# LPDDR4_SDRAM_2.net
KiCad netlist of a schematic drawn in Altium Designer
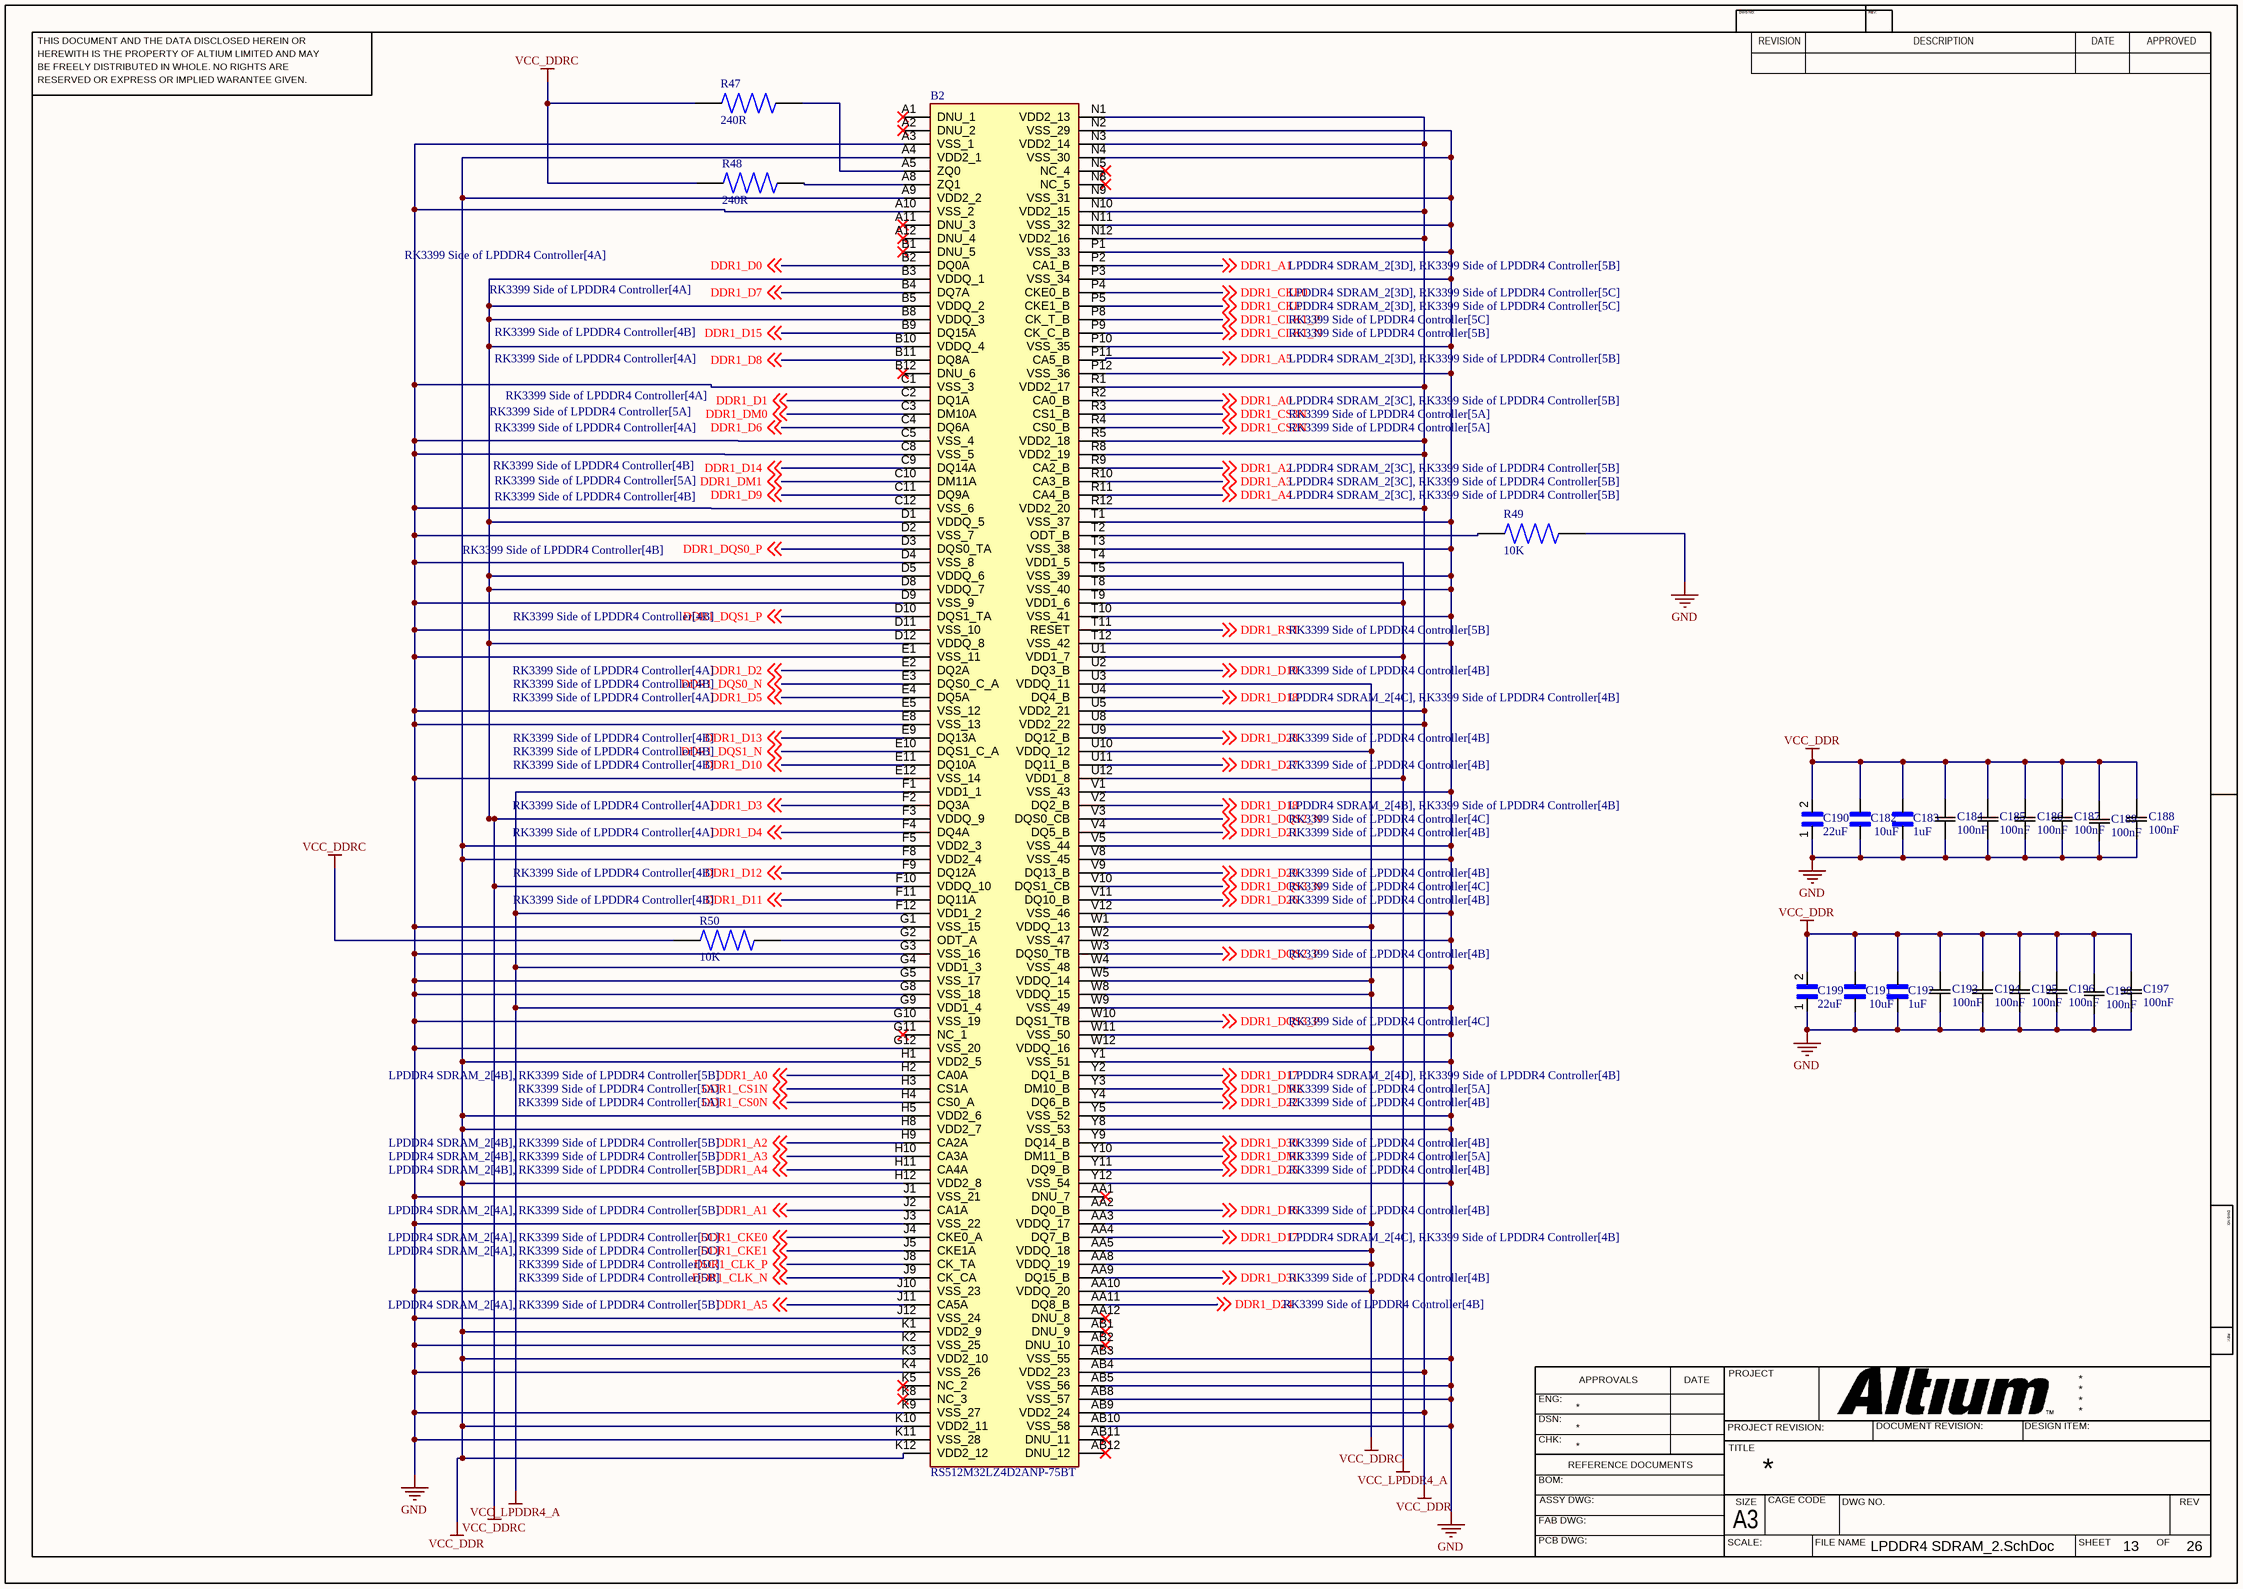
[diagram p0: LPDDR4 SDRAM_2.SchDoc]

(export (version "E")
  (design (tool "Eeschema 10.0.6"))
  (components
    (comp (ref "B2")
      (value "RS512M32LZ4D2ANP-75BT")
      (footprint "BGA200C65P12X22_1000X1500X100")
      (description "BGA-200 New Arrivals ROHS")
      (libsource (lib "RS512M32LZ4D2ANP-75BT") (part "RS512M32LZ4D2ANP-75BT"))
    )
    (comp (ref "C182")
      (value "10uF")
      (footprint "CAPC1005X70N")
      (description "10 ÂµF Â±20% 6.3V Ceramic Capacitor X5R 0402 (1005 Metric)")
      (fields (field (name "MF") "Samsung") (field (name "MP") "CL05A106MQ5NUNC"))
      (libsource (lib "CL05A106MQ5NUNC") (part "CL05A106MQ5NUNC"))
    )
    (comp (ref "C183")
      (value "1uF")
      (footprint "CAPC1005X56N")
      (description "1 ÂµF Â±10% 10V Ceramic Capacitor X5R 0402 (1005 Metric)")
      (fields (field (name "MF") "AVX") (field (name "MP") "0402ZD105KAT4A"))
      (libsource (lib "0402ZD105KAT4A") (part "0402ZD105KAT4A"))
    )
    (comp (ref "C184")
      (value "100nF")
      (footprint "CAP_1005_TDK")
      (description "Description")
      (fields
        (field (name "MANUFACTURER_PART_NUMBER") "C1005X7R1H104M050BB")
        (field (name "COPYRIGHT") "Copyright (C) 2025 Ultra Librarian. All rights reserved.")
      )
      (libsource (lib "C1005X7R1H104M050BB") (part "C1005X7R1H104M050BB"))
    )
    (comp (ref "C185")
      (value "100nF")
      (footprint "CAP_1005_TDK")
      (description "Description")
      (fields
        (field (name "MANUFACTURER_PART_NUMBER") "C1005X7R1H104M050BB")
        (field (name "COPYRIGHT") "Copyright (C) 2025 Ultra Librarian. All rights reserved.")
      )
      (libsource (lib "C1005X7R1H104M050BB") (part "C1005X7R1H104M050BB"))
    )
    (comp (ref "C186")
      (value "100nF")
      (footprint "CAP_1005_TDK")
      (description "Description")
      (fields
        (field (name "MANUFACTURER_PART_NUMBER") "C1005X7R1H104M050BB")
        (field (name "COPYRIGHT") "Copyright (C) 2025 Ultra Librarian. All rights reserved.")
      )
      (libsource (lib "C1005X7R1H104M050BB") (part "C1005X7R1H104M050BB"))
    )
    (comp (ref "C187")
      (value "100nF")
      (footprint "CAP_1005_TDK")
      (description "Description")
      (fields
        (field (name "MANUFACTURER_PART_NUMBER") "C1005X7R1H104M050BB")
        (field (name "COPYRIGHT") "Copyright (C) 2025 Ultra Librarian. All rights reserved.")
      )
      (libsource (lib "C1005X7R1H104M050BB") (part "C1005X7R1H104M050BB"))
    )
    (comp (ref "C188")
      (value "100nF")
      (footprint "CAP_1005_TDK")
      (description "Description")
      (fields
        (field (name "MANUFACTURER_PART_NUMBER") "C1005X7R1H104M050BB")
        (field (name "COPYRIGHT") "Copyright (C) 2025 Ultra Librarian. All rights reserved.")
      )
      (libsource (lib "C1005X7R1H104M050BB") (part "C1005X7R1H104M050BB"))
    )
    (comp (ref "C189")
      (value "100nF")
      (footprint "CAP_1005_TDK")
      (description "Description")
      (fields
        (field (name "MANUFACTURER_PART_NUMBER") "C1005X7R1H104M050BB")
        (field (name "COPYRIGHT") "Copyright (C) 2025 Ultra Librarian. All rights reserved.")
      )
      (libsource (lib "C1005X7R1H104M050BB") (part "C1005X7R1H104M050BB"))
    )
    (comp (ref "C190")
      (value "22uF")
      (footprint "CAPC6050X550N")
      (description "22ÂµF Â±20% 50V Ceramic Capacitor X7S Stacked SMD, 2 J-Lead")
      (fields (field (name "MP") "CKG57NX7S1H226M500JJ"))
      (libsource (lib "CKG57NX7S1H226M500JJ") (part "CKG57NX7S1H226M500JJ"))
    )
    (comp (ref "C191")
      (value "10uF")
      (footprint "CAPC1005X70N")
      (description "10 ÂµF Â±20% 6.3V Ceramic Capacitor X5R 0402 (1005 Metric)")
      (fields (field (name "MF") "Samsung") (field (name "MP") "CL05A106MQ5NUNC"))
      (libsource (lib "CL05A106MQ5NUNC") (part "CL05A106MQ5NUNC"))
    )
    (comp (ref "C192")
      (value "1uF")
      (footprint "CAPC1005X56N")
      (description "1 ÂµF Â±10% 10V Ceramic Capacitor X5R 0402 (1005 Metric)")
      (fields (field (name "MF") "AVX") (field (name "MP") "0402ZD105KAT4A"))
      (libsource (lib "0402ZD105KAT4A") (part "0402ZD105KAT4A"))
    )
    (comp (ref "C193")
      (value "100nF")
      (footprint "CAP_1005_TDK")
      (description "Description")
      (fields
        (field (name "MANUFACTURER_PART_NUMBER") "C1005X7R1H104M050BB")
        (field (name "COPYRIGHT") "Copyright (C) 2025 Ultra Librarian. All rights reserved.")
      )
      (libsource (lib "C1005X7R1H104M050BB") (part "C1005X7R1H104M050BB"))
    )
    (comp (ref "C194")
      (value "100nF")
      (footprint "CAP_1005_TDK")
      (description "Description")
      (fields
        (field (name "MANUFACTURER_PART_NUMBER") "C1005X7R1H104M050BB")
        (field (name "COPYRIGHT") "Copyright (C) 2025 Ultra Librarian. All rights reserved.")
      )
      (libsource (lib "C1005X7R1H104M050BB") (part "C1005X7R1H104M050BB"))
    )
    (comp (ref "C195")
      (value "100nF")
      (footprint "CAP_1005_TDK")
      (description "Description")
      (fields
        (field (name "MANUFACTURER_PART_NUMBER") "C1005X7R1H104M050BB")
        (field (name "COPYRIGHT") "Copyright (C) 2025 Ultra Librarian. All rights reserved.")
      )
      (libsource (lib "C1005X7R1H104M050BB") (part "C1005X7R1H104M050BB"))
    )
    (comp (ref "C196")
      (value "100nF")
      (footprint "CAP_1005_TDK")
      (description "Description")
      (fields
        (field (name "MANUFACTURER_PART_NUMBER") "C1005X7R1H104M050BB")
        (field (name "COPYRIGHT") "Copyright (C) 2025 Ultra Librarian. All rights reserved.")
      )
      (libsource (lib "C1005X7R1H104M050BB") (part "C1005X7R1H104M050BB"))
    )
    (comp (ref "C197")
      (value "100nF")
      (footprint "CAP_1005_TDK")
      (description "Description")
      (fields
        (field (name "MANUFACTURER_PART_NUMBER") "C1005X7R1H104M050BB")
        (field (name "COPYRIGHT") "Copyright (C) 2025 Ultra Librarian. All rights reserved.")
      )
      (libsource (lib "C1005X7R1H104M050BB") (part "C1005X7R1H104M050BB"))
    )
    (comp (ref "C198")
      (value "100nF")
      (footprint "CAP_1005_TDK")
      (description "Description")
      (fields
        (field (name "MANUFACTURER_PART_NUMBER") "C1005X7R1H104M050BB")
        (field (name "COPYRIGHT") "Copyright (C) 2025 Ultra Librarian. All rights reserved.")
      )
      (libsource (lib "C1005X7R1H104M050BB") (part "C1005X7R1H104M050BB"))
    )
    (comp (ref "C199")
      (value "22uF")
      (footprint "CAPC6050X550N")
      (description "22ÂµF Â±20% 50V Ceramic Capacitor X7S Stacked SMD, 2 J-Lead")
      (fields (field (name "MP") "CKG57NX7S1H226M500JJ"))
      (libsource (lib "CKG57NX7S1H226M500JJ") (part "CKG57NX7S1H226M500JJ"))
    )
    (comp (ref "R47")
      (value "240R")
      (footprint "RESC1608X50N")
      (fields (field (name "MP") "ERA6AED241V"))
      (libsource (lib "ERA6AED241V") (part "ERA6AED241V"))
    )
    (comp (ref "R48")
      (value "240R")
      (footprint "RESC1608X50N")
      (fields (field (name "MP") "ERA6AED241V"))
      (libsource (lib "ERA6AED241V") (part "ERA6AED241V"))
    )
    (comp (ref "R49")
      (value "10K")
      (footprint "RESC1608X55N")
      (description "1 kOhms Â±1% 0.1W, 1/10W Chip Resistor 0603 (1608 Metric) - Thick Film")
      (fields (field (name "MF") "Vishay") (field (name "MP") "CRCW06031K00FKECC"))
      (libsource (lib "CRCW06031K00FKECC") (part "CRCW06031K00FKECC"))
    )
    (comp (ref "R50")
      (value "10K")
      (footprint "RESC1608X55N")
      (description "1 kOhms Â±1% 0.1W, 1/10W Chip Resistor 0603 (1608 Metric) - Thick Film")
      (fields (field (name "MF") "Vishay") (field (name "MP") "CRCW06031K00FKECC"))
      (libsource (lib "CRCW06031K00FKECC") (part "CRCW06031K00FKECC"))
    )
  )
  (nets
    (net (code "1") (name "DDR1_A0") (class "Default")
      (node (ref "B2") (pin "H2") (pinfunction "CA0A_H2") (pintype "passive"))
      (node (ref "B2") (pin "R2") (pinfunction "CA0_B_R2") (pintype "passive"))
    )
    (net (code "2") (name "DDR1_A1") (class "Default")
      (node (ref "B2") (pin "J2") (pinfunction "CA1A_J2") (pintype "passive"))
      (node (ref "B2") (pin "P2") (pinfunction "CA1_B_P2") (pintype "passive"))
    )
    (net (code "3") (name "DDR1_A2") (class "Default")
      (node (ref "B2") (pin "H9") (pinfunction "CA2A_H9") (pintype "passive"))
      (node (ref "B2") (pin "R9") (pinfunction "CA2_B_R9") (pintype "passive"))
    )
    (net (code "4") (name "DDR1_A3") (class "Default")
      (node (ref "B2") (pin "H10") (pinfunction "CA3A_H10") (pintype "passive"))
      (node (ref "B2") (pin "R10") (pinfunction "CA3_B_R10") (pintype "passive"))
    )
    (net (code "5") (name "DDR1_A4") (class "Default")
      (node (ref "B2") (pin "H11") (pinfunction "CA4A_H11") (pintype "passive"))
      (node (ref "B2") (pin "R11") (pinfunction "CA4_B_R11") (pintype "passive"))
    )
    (net (code "6") (name "DDR1_A5") (class "Default")
      (node (ref "B2") (pin "J11") (pinfunction "CA5A_J11") (pintype "passive"))
      (node (ref "B2") (pin "P11") (pinfunction "CA5_B_P11") (pintype "passive"))
    )
    (net (code "7") (name "DDR1_CKE0") (class "Default")
      (node (ref "B2") (pin "J4") (pinfunction "CKE0_A_J4") (pintype "passive"))
      (node (ref "B2") (pin "P4") (pinfunction "CKE0_B_P4") (pintype "passive"))
    )
    (net (code "8") (name "DDR1_CKE1") (class "Default")
      (node (ref "B2") (pin "J5") (pinfunction "CKE1A_J5") (pintype "passive"))
      (node (ref "B2") (pin "P5") (pinfunction "CKE1_B_P5") (pintype "passive"))
    )
    (net (code "9") (name "DDR1_CLK1_N") (class "Default")
      (node (ref "B2") (pin "P9") (pinfunction "CK_C_B_P9") (pintype "passive"))
    )
    (net (code "10") (name "DDR1_CLK1_P") (class "Default")
      (node (ref "B2") (pin "P8") (pinfunction "CK_T_B_P8") (pintype "passive"))
    )
    (net (code "11") (name "DDR1_CLK_N") (class "Default")
      (node (ref "B2") (pin "J9") (pinfunction "CK_CA_J9") (pintype "passive"))
    )
    (net (code "12") (name "DDR1_CLK_P") (class "Default")
      (node (ref "B2") (pin "J8") (pinfunction "CK_TA_J8") (pintype "passive"))
    )
    (net (code "13") (name "DDR1_CS0N") (class "Default")
      (node (ref "B2") (pin "H4") (pinfunction "CS0_A_H4") (pintype "passive"))
    )
    (net (code "14") (name "DDR1_CS1N") (class "Default")
      (node (ref "B2") (pin "H3") (pinfunction "CS1A_H3") (pintype "passive"))
    )
    (net (code "15") (name "DDR1_CS2N") (class "Default")
      (node (ref "B2") (pin "R4") (pinfunction "CS0_B_R4") (pintype "passive"))
    )
    (net (code "16") (name "DDR1_CS3N") (class "Default")
      (node (ref "B2") (pin "R3") (pinfunction "CS1_B_R3") (pintype "passive"))
    )
    (net (code "17") (name "DDR1_D0") (class "Default")
      (node (ref "B2") (pin "B2") (pinfunction "DQ0A_B2") (pintype "passive"))
    )
    (net (code "18") (name "DDR1_D1") (class "Default")
      (node (ref "B2") (pin "C2") (pinfunction "DQ1A_C2") (pintype "passive"))
    )
    (net (code "19") (name "DDR1_D2") (class "Default")
      (node (ref "B2") (pin "E2") (pinfunction "DQ2A_E2") (pintype "passive"))
    )
    (net (code "20") (name "DDR1_D3") (class "Default")
      (node (ref "B2") (pin "F2") (pinfunction "DQ3A_F2") (pintype "passive"))
    )
    (net (code "21") (name "DDR1_D4") (class "Default")
      (node (ref "B2") (pin "F4") (pinfunction "DQ4A_F4") (pintype "passive"))
    )
    (net (code "22") (name "DDR1_D5") (class "Default")
      (node (ref "B2") (pin "E4") (pinfunction "DQ5A_E4") (pintype "passive"))
    )
    (net (code "23") (name "DDR1_D6") (class "Default")
      (node (ref "B2") (pin "C4") (pinfunction "DQ6A_C4") (pintype "passive"))
    )
    (net (code "24") (name "DDR1_D7") (class "Default")
      (node (ref "B2") (pin "B4") (pinfunction "DQ7A_B4") (pintype "passive"))
    )
    (net (code "25") (name "DDR1_D8") (class "Default")
      (node (ref "B2") (pin "B11") (pinfunction "DQ8A_B11") (pintype "passive"))
    )
    (net (code "26") (name "DDR1_D9") (class "Default")
      (node (ref "B2") (pin "C11") (pinfunction "DQ9A_C11") (pintype "passive"))
    )
    (net (code "27") (name "DDR1_D10") (class "Default")
      (node (ref "B2") (pin "E11") (pinfunction "DQ10A_E11") (pintype "passive"))
    )
    (net (code "28") (name "DDR1_D11") (class "Default")
      (node (ref "B2") (pin "F11") (pinfunction "DQ11A_F11") (pintype "passive"))
    )
    (net (code "29") (name "DDR1_D12") (class "Default")
      (node (ref "B2") (pin "F9") (pinfunction "DQ12A_F9") (pintype "passive"))
    )
    (net (code "30") (name "DDR1_D13") (class "Default")
      (node (ref "B2") (pin "E9") (pinfunction "DQ13A_E9") (pintype "passive"))
    )
    (net (code "31") (name "DDR1_D14") (class "Default")
      (node (ref "B2") (pin "C9") (pinfunction "DQ14A_C9") (pintype "passive"))
    )
    (net (code "32") (name "DDR1_D15") (class "Default")
      (node (ref "B2") (pin "B9") (pinfunction "DQ15A_B9") (pintype "passive"))
    )
    (net (code "33") (name "DDR1_D16") (class "Default")
      (node (ref "B2") (pin "AA2") (pinfunction "DQ0_B_AA2") (pintype "passive"))
    )
    (net (code "34") (name "DDR1_D17") (class "Default")
      (node (ref "B2") (pin "AA4") (pinfunction "DQ7_B_AA4") (pintype "passive"))
      (node (ref "B2") (pin "Y2") (pinfunction "DQ1_B_Y2") (pintype "passive"))
    )
    (net (code "35") (name "DDR1_D18") (class "Default")
      (node (ref "B2") (pin "U4") (pinfunction "DQ4_B_U4") (pintype "passive"))
      (node (ref "B2") (pin "V2") (pinfunction "DQ2_B_V2") (pintype "passive"))
    )
    (net (code "36") (name "DDR1_D19") (class "Default")
      (node (ref "B2") (pin "U2") (pinfunction "DQ3_B_U2") (pintype "passive"))
    )
    (net (code "37") (name "DDR1_D21") (class "Default")
      (node (ref "B2") (pin "V4") (pinfunction "DQ5_B_V4") (pintype "passive"))
    )
    (net (code "38") (name "DDR1_D22") (class "Default")
      (node (ref "B2") (pin "Y4") (pinfunction "DQ6_B_Y4") (pintype "passive"))
    )
    (net (code "39") (name "DDR1_D24") (class "Default")
      (node (ref "B2") (pin "AA11") (pinfunction "DQ8_B_AA11") (pintype "passive"))
    )
    (net (code "40") (name "DDR1_D25") (class "Default")
      (node (ref "B2") (pin "Y11") (pinfunction "DQ9_B_Y11") (pintype "passive"))
    )
    (net (code "41") (name "DDR1_D26") (class "Default")
      (node (ref "B2") (pin "V11") (pinfunction "DQ10_B_V11") (pintype "passive"))
    )
    (net (code "42") (name "DDR1_D27") (class "Default")
      (node (ref "B2") (pin "U11") (pinfunction "DQ11_B_U11") (pintype "passive"))
    )
    (net (code "43") (name "DDR1_D28") (class "Default")
      (node (ref "B2") (pin "U9") (pinfunction "DQ12_B_U9") (pintype "passive"))
    )
    (net (code "44") (name "DDR1_D29") (class "Default")
      (node (ref "B2") (pin "V9") (pinfunction "DQ13_B_V9") (pintype "passive"))
    )
    (net (code "45") (name "DDR1_D30") (class "Default")
      (node (ref "B2") (pin "Y9") (pinfunction "DQ14_B_Y9") (pintype "passive"))
    )
    (net (code "46") (name "DDR1_D31") (class "Default")
      (node (ref "B2") (pin "AA9") (pinfunction "DQ15_B_AA9") (pintype "passive"))
    )
    (net (code "47") (name "DDR1_DM0") (class "Default")
      (node (ref "B2") (pin "C3") (pinfunction "DM10A_C3") (pintype "passive"))
    )
    (net (code "48") (name "DDR1_DM1") (class "Default")
      (node (ref "B2") (pin "C10") (pinfunction "DM11A_C10") (pintype "passive"))
    )
    (net (code "49") (name "DDR1_DM2") (class "Default")
      (node (ref "B2") (pin "Y3") (pinfunction "DM10_B_Y3") (pintype "passive"))
    )
    (net (code "50") (name "DDR1_DM3") (class "Default")
      (node (ref "B2") (pin "Y10") (pinfunction "DM11_B_Y10") (pintype "passive"))
    )
    (net (code "51") (name "DDR1_DQS0_N") (class "Default")
      (node (ref "B2") (pin "E3") (pinfunction "DQS0_C_A_E3") (pintype "passive"))
    )
    (net (code "52") (name "DDR1_DQS0_P") (class "Default")
      (node (ref "B2") (pin "D3") (pinfunction "DQS0_TA_D3") (pintype "passive"))
    )
    (net (code "53") (name "DDR1_DQS1_N") (class "Default")
      (node (ref "B2") (pin "E10") (pinfunction "DQS1_C_A_E10") (pintype "passive"))
    )
    (net (code "54") (name "DDR1_DQS1_P") (class "Default")
      (node (ref "B2") (pin "D10") (pinfunction "DQS1_TA_D10") (pintype "passive"))
    )
    (net (code "55") (name "DDR1_DQS2_N") (class "Default")
      (node (ref "B2") (pin "V3") (pinfunction "DQS0_CB_V3") (pintype "passive"))
    )
    (net (code "56") (name "DDR1_DQS2_P") (class "Default")
      (node (ref "B2") (pin "W3") (pinfunction "DQS0_TB_W3") (pintype "passive"))
    )
    (net (code "57") (name "DDR1_DQS3_N") (class "Default")
      (node (ref "B2") (pin "V10") (pinfunction "DQS1_CB_V10") (pintype "passive"))
    )
    (net (code "58") (name "DDR1_DQS3_P") (class "Default")
      (node (ref "B2") (pin "W10") (pinfunction "DQS1_TB_W10") (pintype "passive"))
    )
    (net (code "59") (name "DDR1_RST") (class "Default")
      (node (ref "B2") (pin "T11") (pinfunction "RESET_T11") (pintype "passive"))
    )
    (net (code "60") (name "GND") (class "Default")
      (node (ref "B2") (pin "A10") (pinfunction "VSS_2_A10") (pintype "passive"))
      (node (ref "B2") (pin "A3") (pinfunction "VSS_1_A3") (pintype "passive"))
      (node (ref "B2") (pin "AB10") (pinfunction "VSS_58_AB10") (pintype "passive"))
      (node (ref "B2") (pin "AB3") (pinfunction "VSS_55_AB3") (pintype "passive"))
      (node (ref "B2") (pin "AB5") (pinfunction "VSS_56_AB5") (pintype "passive"))
      (node (ref "B2") (pin "AB8") (pinfunction "VSS_57_AB8") (pintype "passive"))
      (node (ref "B2") (pin "C1") (pinfunction "VSS_3_C1") (pintype "passive"))
      (node (ref "B2") (pin "C12") (pinfunction "VSS_6_C12") (pintype "passive"))
      (node (ref "B2") (pin "C5") (pinfunction "VSS_4_C5") (pintype "passive"))
      (node (ref "B2") (pin "C8") (pinfunction "VSS_5_C8") (pintype "passive"))
      (node (ref "B2") (pin "D11") (pinfunction "VSS_10_D11") (pintype "passive"))
      (node (ref "B2") (pin "D2") (pinfunction "VSS_7_D2") (pintype "passive"))
      (node (ref "B2") (pin "D4") (pinfunction "VSS_8_D4") (pintype "passive"))
      (node (ref "B2") (pin "D9") (pinfunction "VSS_9_D9") (pintype "passive"))
      (node (ref "B2") (pin "E1") (pinfunction "VSS_11_E1") (pintype "passive"))
      (node (ref "B2") (pin "E12") (pinfunction "VSS_14_E12") (pintype "passive"))
      (node (ref "B2") (pin "E5") (pinfunction "VSS_12_E5") (pintype "passive"))
      (node (ref "B2") (pin "E8") (pinfunction "VSS_13_E8") (pintype "passive"))
      (node (ref "B2") (pin "G1") (pinfunction "VSS_15_G1") (pintype "passive"))
      (node (ref "B2") (pin "G10") (pinfunction "VSS_19_G10") (pintype "passive"))
      (node (ref "B2") (pin "G12") (pinfunction "VSS_20_G12") (pintype "passive"))
      (node (ref "B2") (pin "G3") (pinfunction "VSS_16_G3") (pintype "passive"))
      (node (ref "B2") (pin "G5") (pinfunction "VSS_17_G5") (pintype "passive"))
      (node (ref "B2") (pin "G8") (pinfunction "VSS_18_G8") (pintype "passive"))
      (node (ref "B2") (pin "J1") (pinfunction "VSS_21_J1") (pintype "passive"))
      (node (ref "B2") (pin "J10") (pinfunction "VSS_23_J10") (pintype "passive"))
      (node (ref "B2") (pin "J12") (pinfunction "VSS_24_J12") (pintype "passive"))
      (node (ref "B2") (pin "J3") (pinfunction "VSS_22_J3") (pintype "passive"))
      (node (ref "B2") (pin "K11") (pinfunction "VSS_28_K11") (pintype "passive"))
      (node (ref "B2") (pin "K2") (pinfunction "VSS_25_K2") (pintype "passive"))
      (node (ref "B2") (pin "K4") (pinfunction "VSS_26_K4") (pintype "passive"))
      (node (ref "B2") (pin "K9") (pinfunction "VSS_27_K9") (pintype "passive"))
      (node (ref "B2") (pin "N11") (pinfunction "VSS_32_N11") (pintype "passive"))
      (node (ref "B2") (pin "N2") (pinfunction "VSS_29_N2") (pintype "passive"))
      (node (ref "B2") (pin "N4") (pinfunction "VSS_30_N4") (pintype "passive"))
      (node (ref "B2") (pin "N9") (pinfunction "VSS_31_N9") (pintype "passive"))
      (node (ref "B2") (pin "P1") (pinfunction "VSS_33_P1") (pintype "passive"))
      (node (ref "B2") (pin "P10") (pinfunction "VSS_35_P10") (pintype "passive"))
      (node (ref "B2") (pin "P12") (pinfunction "VSS_36_P12") (pintype "passive"))
      (node (ref "B2") (pin "P3") (pinfunction "VSS_34_P3") (pintype "passive"))
      (node (ref "B2") (pin "T1") (pinfunction "VSS_37_T1") (pintype "passive"))
      (node (ref "B2") (pin "T10") (pinfunction "VSS_41_T10") (pintype "passive"))
      (node (ref "B2") (pin "T12") (pinfunction "VSS_42_T12") (pintype "passive"))
      (node (ref "B2") (pin "T3") (pinfunction "VSS_38_T3") (pintype "passive"))
      (node (ref "B2") (pin "T5") (pinfunction "VSS_39_T5") (pintype "passive"))
      (node (ref "B2") (pin "T8") (pinfunction "VSS_40_T8") (pintype "passive"))
      (node (ref "B2") (pin "V1") (pinfunction "VSS_43_V1") (pintype "passive"))
      (node (ref "B2") (pin "V12") (pinfunction "VSS_46_V12") (pintype "passive"))
      (node (ref "B2") (pin "V5") (pinfunction "VSS_44_V5") (pintype "passive"))
      (node (ref "B2") (pin "V8") (pinfunction "VSS_45_V8") (pintype "passive"))
      (node (ref "B2") (pin "W11") (pinfunction "VSS_50_W11") (pintype "passive"))
      (node (ref "B2") (pin "W2") (pinfunction "VSS_47_W2") (pintype "passive"))
      (node (ref "B2") (pin "W4") (pinfunction "VSS_48_W4") (pintype "passive"))
      (node (ref "B2") (pin "W9") (pinfunction "VSS_49_W9") (pintype "passive"))
      (node (ref "B2") (pin "Y1") (pinfunction "VSS_51_Y1") (pintype "passive"))
      (node (ref "B2") (pin "Y12") (pinfunction "VSS_54_Y12") (pintype "passive"))
      (node (ref "B2") (pin "Y5") (pinfunction "VSS_52_Y5") (pintype "passive"))
      (node (ref "B2") (pin "Y8") (pinfunction "VSS_53_Y8") (pintype "passive"))
      (node (ref "C182") (pin "1") (pinfunction "1_1") (pintype "passive"))
      (node (ref "C183") (pin "1") (pinfunction "1_1") (pintype "passive"))
      (node (ref "C184") (pin "1") (pinfunction "1_1") (pintype "passive"))
      (node (ref "C185") (pin "1") (pinfunction "1_1") (pintype "passive"))
      (node (ref "C186") (pin "1") (pinfunction "1_1") (pintype "passive"))
      (node (ref "C187") (pin "1") (pinfunction "1_1") (pintype "passive"))
      (node (ref "C188") (pin "1") (pinfunction "1_1") (pintype "passive"))
      (node (ref "C189") (pin "1") (pinfunction "1_1") (pintype "passive"))
      (node (ref "C190") (pin "1") (pinfunction "1_1") (pintype "passive"))
      (node (ref "C191") (pin "1") (pinfunction "1_1") (pintype "passive"))
      (node (ref "C192") (pin "1") (pinfunction "1_1") (pintype "passive"))
      (node (ref "C193") (pin "1") (pinfunction "1_1") (pintype "passive"))
      (node (ref "C194") (pin "1") (pinfunction "1_1") (pintype "passive"))
      (node (ref "C195") (pin "1") (pinfunction "1_1") (pintype "passive"))
      (node (ref "C196") (pin "1") (pinfunction "1_1") (pintype "passive"))
      (node (ref "C197") (pin "1") (pinfunction "1_1") (pintype "passive"))
      (node (ref "C198") (pin "1") (pinfunction "1_1") (pintype "passive"))
      (node (ref "C199") (pin "1") (pinfunction "1_1") (pintype "passive"))
      (node (ref "R49") (pin "2") (pinfunction "2_2") (pintype "passive"))
    )
    (net (code "61") (name "Net-(B2-ODT_A)") (class "Default")
      (node (ref "B2") (pin "G2") (pinfunction "ODT_A_G2") (pintype "passive"))
      (node (ref "R50") (pin "1") (pinfunction "1_1") (pintype "passive"))
    )
    (net (code "62") (name "Net-(B2-ODT_B)") (class "Default")
      (node (ref "B2") (pin "T2") (pinfunction "ODT_B_T2") (pintype "passive"))
      (node (ref "R49") (pin "1") (pinfunction "1_1") (pintype "passive"))
    )
    (net (code "63") (name "Net-(B2-ZQ0)") (class "Default")
      (node (ref "B2") (pin "A5") (pinfunction "ZQ0_A5") (pintype "passive"))
      (node (ref "R47") (pin "2") (pinfunction "2_2") (pintype "passive"))
    )
    (net (code "64") (name "Net-(B2-ZQ1)") (class "Default")
      (node (ref "B2") (pin "A8") (pinfunction "ZQ1_A8") (pintype "passive"))
      (node (ref "R48") (pin "2") (pinfunction "2_2") (pintype "passive"))
    )
    (net (code "65") (name "VCC_DDR") (class "Default")
      (node (ref "B2") (pin "A4") (pinfunction "VDD2_1_A4") (pintype "passive"))
      (node (ref "B2") (pin "A9") (pinfunction "VDD2_2_A9") (pintype "passive"))
      (node (ref "B2") (pin "AB4") (pinfunction "VDD2_23_AB4") (pintype "passive"))
      (node (ref "B2") (pin "AB9") (pinfunction "VDD2_24_AB9") (pintype "passive"))
      (node (ref "B2") (pin "F5") (pinfunction "VDD2_3_F5") (pintype "passive"))
      (node (ref "B2") (pin "F8") (pinfunction "VDD2_4_F8") (pintype "passive"))
      (node (ref "B2") (pin "H1") (pinfunction "VDD2_5_H1") (pintype "passive"))
      (node (ref "B2") (pin "H12") (pinfunction "VDD2_8_H12") (pintype "passive"))
      (node (ref "B2") (pin "H5") (pinfunction "VDD2_6_H5") (pintype "passive"))
      (node (ref "B2") (pin "H8") (pinfunction "VDD2_7_H8") (pintype "passive"))
      (node (ref "B2") (pin "K1") (pinfunction "VDD2_9_K1") (pintype "passive"))
      (node (ref "B2") (pin "K10") (pinfunction "VDD2_11_K10") (pintype "passive"))
      (node (ref "B2") (pin "K12") (pinfunction "VDD2_12_K12") (pintype "passive"))
      (node (ref "B2") (pin "K3") (pinfunction "VDD2_10_K3") (pintype "passive"))
      (node (ref "B2") (pin "N1") (pinfunction "VDD2_13_N1") (pintype "passive"))
      (node (ref "B2") (pin "N10") (pinfunction "VDD2_15_N10") (pintype "passive"))
      (node (ref "B2") (pin "N12") (pinfunction "VDD2_16_N12") (pintype "passive"))
      (node (ref "B2") (pin "N3") (pinfunction "VDD2_14_N3") (pintype "passive"))
      (node (ref "B2") (pin "R1") (pinfunction "VDD2_17_R1") (pintype "passive"))
      (node (ref "B2") (pin "R12") (pinfunction "VDD2_20_R12") (pintype "passive"))
      (node (ref "B2") (pin "R5") (pinfunction "VDD2_18_R5") (pintype "passive"))
      (node (ref "B2") (pin "R8") (pinfunction "VDD2_19_R8") (pintype "passive"))
      (node (ref "B2") (pin "U5") (pinfunction "VDD2_21_U5") (pintype "passive"))
      (node (ref "B2") (pin "U8") (pinfunction "VDD2_22_U8") (pintype "passive"))
      (node (ref "C182") (pin "2") (pinfunction "2_2") (pintype "passive"))
      (node (ref "C183") (pin "2") (pinfunction "2_2") (pintype "passive"))
      (node (ref "C184") (pin "2") (pinfunction "2_2") (pintype "passive"))
      (node (ref "C185") (pin "2") (pinfunction "2_2") (pintype "passive"))
      (node (ref "C186") (pin "2") (pinfunction "2_2") (pintype "passive"))
      (node (ref "C187") (pin "2") (pinfunction "2_2") (pintype "passive"))
      (node (ref "C188") (pin "2") (pinfunction "2_2") (pintype "passive"))
      (node (ref "C189") (pin "2") (pinfunction "2_2") (pintype "passive"))
      (node (ref "C190") (pin "2") (pinfunction "2_2") (pintype "passive"))
      (node (ref "C191") (pin "2") (pinfunction "2_2") (pintype "passive"))
      (node (ref "C192") (pin "2") (pinfunction "2_2") (pintype "passive"))
      (node (ref "C193") (pin "2") (pinfunction "2_2") (pintype "passive"))
      (node (ref "C194") (pin "2") (pinfunction "2_2") (pintype "passive"))
      (node (ref "C195") (pin "2") (pinfunction "2_2") (pintype "passive"))
      (node (ref "C196") (pin "2") (pinfunction "2_2") (pintype "passive"))
      (node (ref "C197") (pin "2") (pinfunction "2_2") (pintype "passive"))
      (node (ref "C198") (pin "2") (pinfunction "2_2") (pintype "passive"))
      (node (ref "C199") (pin "2") (pinfunction "2_2") (pintype "passive"))
    )
    (net (code "66") (name "VCC_DDRC") (class "Default")
      (node (ref "B2") (pin "AA10") (pinfunction "VDDQ_20_AA10") (pintype "passive"))
      (node (ref "B2") (pin "AA3") (pinfunction "VDDQ_17_AA3") (pintype "passive"))
      (node (ref "B2") (pin "AA5") (pinfunction "VDDQ_18_AA5") (pintype "passive"))
      (node (ref "B2") (pin "AA8") (pinfunction "VDDQ_19_AA8") (pintype "passive"))
      (node (ref "B2") (pin "B10") (pinfunction "VDDQ_4_B10") (pintype "passive"))
      (node (ref "B2") (pin "B3") (pinfunction "VDDQ_1_B3") (pintype "passive"))
      (node (ref "B2") (pin "B5") (pinfunction "VDDQ_2_B5") (pintype "passive"))
      (node (ref "B2") (pin "B8") (pinfunction "VDDQ_3_B8") (pintype "passive"))
      (node (ref "B2") (pin "D1") (pinfunction "VDDQ_5_D1") (pintype "passive"))
      (node (ref "B2") (pin "D12") (pinfunction "VDDQ_8_D12") (pintype "passive"))
      (node (ref "B2") (pin "D5") (pinfunction "VDDQ_6_D5") (pintype "passive"))
      (node (ref "B2") (pin "D8") (pinfunction "VDDQ_7_D8") (pintype "passive"))
      (node (ref "B2") (pin "F10") (pinfunction "VDDQ_10_F10") (pintype "passive"))
      (node (ref "B2") (pin "F3") (pinfunction "VDDQ_9_F3") (pintype "passive"))
      (node (ref "B2") (pin "U10") (pinfunction "VDDQ_12_U10") (pintype "passive"))
      (node (ref "B2") (pin "U3") (pinfunction "VDDQ_11_U3") (pintype "passive"))
      (node (ref "B2") (pin "W1") (pinfunction "VDDQ_13_W1") (pintype "passive"))
      (node (ref "B2") (pin "W12") (pinfunction "VDDQ_16_W12") (pintype "passive"))
      (node (ref "B2") (pin "W5") (pinfunction "VDDQ_14_W5") (pintype "passive"))
      (node (ref "B2") (pin "W8") (pinfunction "VDDQ_15_W8") (pintype "passive"))
      (node (ref "R47") (pin "1") (pinfunction "1_1") (pintype "passive"))
      (node (ref "R48") (pin "1") (pinfunction "1_1") (pintype "passive"))
      (node (ref "R50") (pin "2") (pinfunction "2_2") (pintype "passive"))
    )
    (net (code "67") (name "VCC_LPDDR4_A") (class "Default")
      (node (ref "B2") (pin "F1") (pinfunction "VDD1_1_F1") (pintype "passive"))
      (node (ref "B2") (pin "F12") (pinfunction "VDD1_2_F12") (pintype "passive"))
      (node (ref "B2") (pin "G4") (pinfunction "VDD1_3_G4") (pintype "passive"))
      (node (ref "B2") (pin "G9") (pinfunction "VDD1_4_G9") (pintype "passive"))
      (node (ref "B2") (pin "T4") (pinfunction "VDD1_5_T4") (pintype "passive"))
      (node (ref "B2") (pin "T9") (pinfunction "VDD1_6_T9") (pintype "passive"))
      (node (ref "B2") (pin "U1") (pinfunction "VDD1_7_U1") (pintype "passive"))
      (node (ref "B2") (pin "U12") (pinfunction "VDD1_8_U12") (pintype "passive"))
    )
    (net (code "68") (name "unconnected-(B2-DNU_1-PadA1)") (class "Default")
      (node (ref "B2") (pin "A1") (pinfunction "DNU_1_A1") (pintype "passive+no_connect"))
    )
    (net (code "69") (name "unconnected-(B2-DNU_2-PadA2)") (class "Default")
      (node (ref "B2") (pin "A2") (pinfunction "DNU_2_A2") (pintype "passive+no_connect"))
    )
    (net (code "70") (name "unconnected-(B2-DNU_3-PadA11)") (class "Default")
      (node (ref "B2") (pin "A11") (pinfunction "DNU_3_A11") (pintype "passive+no_connect"))
    )
    (net (code "71") (name "unconnected-(B2-DNU_4-PadA12)") (class "Default")
      (node (ref "B2") (pin "A12") (pinfunction "DNU_4_A12") (pintype "passive+no_connect"))
    )
    (net (code "72") (name "unconnected-(B2-DNU_5-PadB1)") (class "Default")
      (node (ref "B2") (pin "B1") (pinfunction "DNU_5_B1") (pintype "passive+no_connect"))
    )
    (net (code "73") (name "unconnected-(B2-DNU_6-PadB12)") (class "Default")
      (node (ref "B2") (pin "B12") (pinfunction "DNU_6_B12") (pintype "passive+no_connect"))
    )
    (net (code "74") (name "unconnected-(B2-DNU_7-PadAA1)") (class "Default")
      (node (ref "B2") (pin "AA1") (pinfunction "DNU_7_AA1") (pintype "passive+no_connect"))
    )
    (net (code "75") (name "unconnected-(B2-DNU_8-PadAA12)") (class "Default")
      (node (ref "B2") (pin "AA12") (pinfunction "DNU_8_AA12") (pintype "passive+no_connect"))
    )
    (net (code "76") (name "unconnected-(B2-DNU_9-PadAB1)") (class "Default")
      (node (ref "B2") (pin "AB1") (pinfunction "DNU_9_AB1") (pintype "passive+no_connect"))
    )
    (net (code "77") (name "unconnected-(B2-DNU_10-PadAB2)") (class "Default")
      (node (ref "B2") (pin "AB2") (pinfunction "DNU_10_AB2") (pintype "passive+no_connect"))
    )
    (net (code "78") (name "unconnected-(B2-DNU_11-PadAB11)") (class "Default")
      (node (ref "B2") (pin "AB11") (pinfunction "DNU_11_AB11") (pintype "passive+no_connect"))
    )
    (net (code "79") (name "unconnected-(B2-DNU_12-PadAB12)") (class "Default")
      (node (ref "B2") (pin "AB12") (pinfunction "DNU_12_AB12") (pintype "passive+no_connect"))
    )
    (net (code "80") (name "unconnected-(B2-NC_1-PadG11)") (class "Default")
      (node (ref "B2") (pin "G11") (pinfunction "NC_1_G11") (pintype "passive+no_connect"))
    )
    (net (code "81") (name "unconnected-(B2-NC_2-PadK5)") (class "Default")
      (node (ref "B2") (pin "K5") (pinfunction "NC_2_K5") (pintype "passive+no_connect"))
    )
    (net (code "82") (name "unconnected-(B2-NC_3-PadK8)") (class "Default")
      (node (ref "B2") (pin "K8") (pinfunction "NC_3_K8") (pintype "passive+no_connect"))
    )
    (net (code "83") (name "unconnected-(B2-NC_4-PadN5)") (class "Default")
      (node (ref "B2") (pin "N5") (pinfunction "NC_4_N5") (pintype "passive+no_connect"))
    )
    (net (code "84") (name "unconnected-(B2-NC_5-PadN8)") (class "Default")
      (node (ref "B2") (pin "N8") (pinfunction "NC_5_N8") (pintype "passive+no_connect"))
    )
  )
)
